# uC_Essentials.net
KiCad netlist of a schematic drawn in Altium Designer
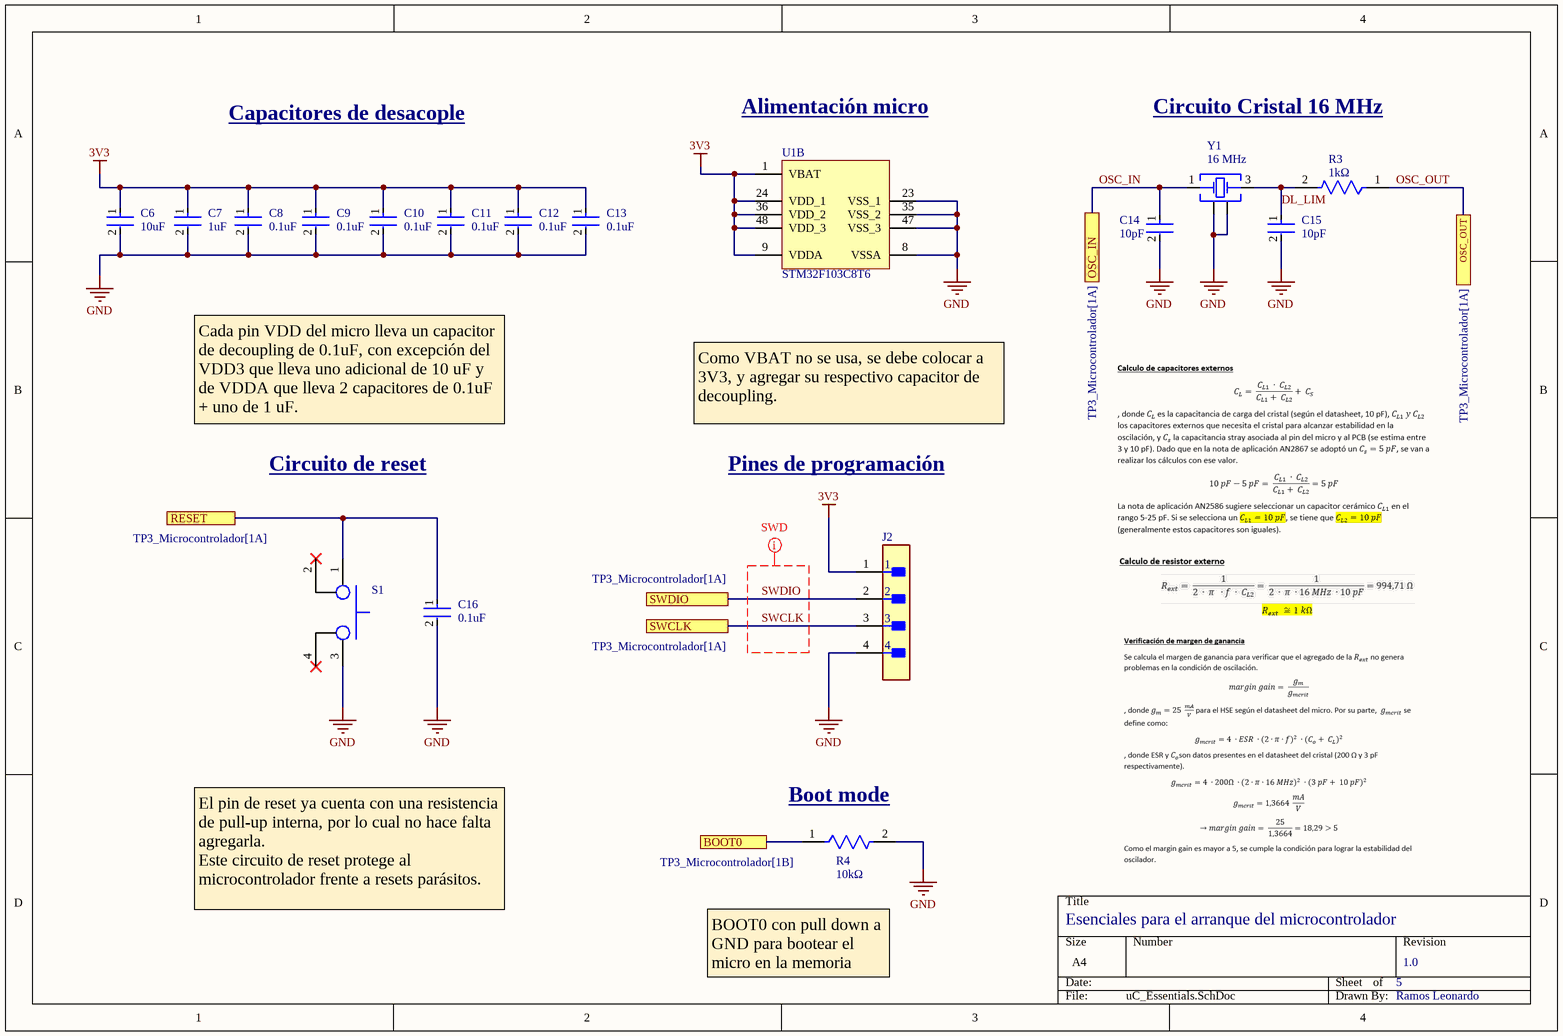
[diagram p0: uC_Essentials.SchDoc]

(export (version "E")
  (design (tool "Eeschema 10.0.6"))
  (components
    (comp (ref "C6")
      (value "10uF")
      (footprint "FP-CC0805-0_85-MFG")
      (description "CAP CER 4.7UF 25V X7R 0805")
      (fields (field (name "MANUFACTURER PART NUMBER") "CC0805KRX7R8BB104") (field (name "TOLERANCE") "0.1"))
      (libsource (lib "Altium Content Vault") (part "11868f565c42a9108669ba33697ecf6"))
    )
    (comp (ref "C7")
      (value "1uF")
      (footprint "FP-CC0805-0_85-MFG")
      (description "CAP CER 1UF 25V X7R 0805")
      (fields (field (name "MANUFACTURER PART NUMBER") "CC0805KRX7R8BB104") (field (name "TOLERANCE") "0.1"))
      (libsource (lib "Altium Content Vault") (part "11868f565c42a9108669ba33697ecf6"))
    )
    (comp (ref "C8")
      (value "0.1uF")
      (footprint "FP-CC0805-0_85-MFG")
      (description "CAP CER 0.1UF 25V X7R 0805")
      (fields (field (name "MANUFACTURER PART NUMBER") "CC0805KRX7R8BB104") (field (name "TOLERANCE") "0.1"))
      (libsource (lib "Altium Content Vault") (part "11868f565c42a9108669ba33697ecf6"))
    )
    (comp (ref "C9")
      (value "0.1uF")
      (footprint "FP-CC0805-0_85-MFG")
      (description "CAP CER 0.1UF 25V X7R 0805")
      (fields (field (name "MANUFACTURER PART NUMBER") "CC0805KRX7R8BB104") (field (name "TOLERANCE") "0.1"))
      (libsource (lib "Altium Content Vault") (part "11868f565c42a9108669ba33697ecf6"))
    )
    (comp (ref "C10")
      (value "0.1uF")
      (footprint "FP-CC0805-0_85-MFG")
      (description "CAP CER 0.1UF 25V X7R 0805")
      (fields (field (name "MANUFACTURER PART NUMBER") "CC0805KRX7R8BB104") (field (name "TOLERANCE") "0.1"))
      (libsource (lib "Altium Content Vault") (part "11868f565c42a9108669ba33697ecf6"))
    )
    (comp (ref "C11")
      (value "0.1uF")
      (footprint "FP-CC0805-0_85-MFG")
      (description "CAP CER 0.1UF 25V X7R 0805")
      (fields (field (name "MANUFACTURER PART NUMBER") "CC0805KRX7R8BB104") (field (name "TOLERANCE") "0.1"))
      (libsource (lib "Altium Content Vault") (part "11868f565c42a9108669ba33697ecf6"))
    )
    (comp (ref "C12")
      (value "0.1uF")
      (footprint "FP-CC0805-0_85-MFG")
      (description "CAP CER 0.1UF 25V X7R 0805")
      (fields (field (name "MANUFACTURER PART NUMBER") "CC0805KRX7R8BB104") (field (name "TOLERANCE") "0.1"))
      (libsource (lib "Altium Content Vault") (part "11868f565c42a9108669ba33697ecf6"))
    )
    (comp (ref "C13")
      (value "0.1uF")
      (footprint "FP-CC0805-0_85-MFG")
      (description "CAP CER 0.1UF 25V X7R 0805")
      (fields (field (name "MANUFACTURER PART NUMBER") "CC0805KRX7R8BB104") (field (name "TOLERANCE") "0.1"))
      (libsource (lib "Altium Content Vault") (part "11868f565c42a9108669ba33697ecf6"))
    )
    (comp (ref "C14")
      (value "10pF")
      (footprint "FP-CC0805-0_85-MFG")
      (description "CAP CER 10pF 25V X7R 0805")
      (fields (field (name "MANUFACTURER PART NUMBER") "CC0805KRX7R8BB104") (field (name "TOLERANCE") "0.1"))
      (libsource (lib "Altium Content Vault") (part "11868f565c42a9108669ba33697ecf6"))
    )
    (comp (ref "C15")
      (value "10pF")
      (footprint "FP-CC0805-0_85-MFG")
      (description "CAP CER 10pF 25V X7R 0805")
      (fields (field (name "MANUFACTURER PART NUMBER") "CC0805KRX7R8BB104") (field (name "TOLERANCE") "0.1"))
      (libsource (lib "Altium Content Vault") (part "11868f565c42a9108669ba33697ecf6"))
    )
    (comp (ref "C16")
      (value "0.1uF")
      (footprint "FP-CC0805-0_85-MFG")
      (description "CAP CER 0.1UF 25V X7R 0805")
      (fields (field (name "MANUFACTURER PART NUMBER") "CC0805KRX7R8BB104") (field (name "TOLERANCE") "0.1"))
      (libsource (lib "Altium Content Vault") (part "11868f565c42a9108669ba33697ecf6"))
    )
    (comp (ref "J2")
      (value "HTSW-104-07-G-S")
      (footprint "FP-HTSW-104-07-G-S-MFG")
      (description "CONN HEADER VERT 4POS 2.54MM")
      (libsource (lib "Altium Content Vault") (part "299a8cea1bdcbc3624fe62c390fa72c"))
    )
    (comp (ref "R3")
      (value "CRCW08054K70JNEA")
      (footprint "FP-CRCW0805-e3-IPC_B")
      (description "RES Thick Film, 1kΩ, 5%, 0.125W, 200ppm/°C, 0805")
      (fields (field (name "TOLERANCE") "5%") (field (name "RESISTANCE") "1kΩ"))
      (libsource (lib "Altium Content Vault") (part "1029c3af85768c4190bb7ad29bc67b5"))
    )
    (comp (ref "R4")
      (value "CRCW08054K70JNEA")
      (footprint "FP-CRCW0805-e3-IPC_B")
      (description "RES Thick Film, 5%, 0.125W, 200ppm/°C, 0805")
      (fields (field (name "TOLERANCE") "5%") (field (name "RESISTANCE") "10kΩ"))
      (libsource (lib "Altium Content Vault") (part "1029c3af85768c4190bb7ad29bc67b5"))
    )
    (comp (ref "S1")
      (value "Tactile push button")
      (footprint "FP-B3W-1000-MFG")
      (libsource (lib "Componentes_custom") (part "Tactile push button"))
    )
    (comp (ref "U1")
      (value "STM32F103C8T6")
      (footprint "STM-LQFP48_L")
      (libsource (lib "Componentes_custom") (part "CMP-0237-00215-3"))
    )
    (comp (ref "Y1")
      (value "16 MHz")
      (footprint "WE-XTAL_IQXC-42")
      (description "830108288709 WE-XTAL Quartz Crystal")
      (libsource (lib "Altium Content Vault") (part "WE-XTAL_IQXC-42"))
    )
  )
  (nets
    (net (code "1") (name "/BOOT0") (class "Default")
      (node (ref "R4") (pin "1") (pinfunction "1_1") (pintype "passive"))
    )
    (net (code "2") (name "/DL_LIM") (class "Default")
      (node (ref "C15") (pin "1") (pinfunction "1_1") (pintype "passive"))
      (node (ref "R3") (pin "2") (pinfunction "2_2") (pintype "passive"))
      (node (ref "Y1") (pin "3") (pinfunction "Crystal_3") (pintype "passive"))
    )
    (net (code "3") (name "/OSC_IN") (class "Default")
      (node (ref "C14") (pin "1") (pinfunction "1_1") (pintype "passive"))
      (node (ref "Y1") (pin "1") (pinfunction "Crystal_1") (pintype "passive"))
    )
    (net (code "4") (name "/OSC_OUT") (class "Default")
      (node (ref "R3") (pin "1") (pinfunction "1_1") (pintype "passive"))
    )
    (net (code "5") (name "/RESET") (class "Default")
      (node (ref "C16") (pin "1") (pinfunction "1_1") (pintype "passive"))
      (node (ref "S1") (pin "1") (pinfunction "1_1") (pintype "passive"))
    )
    (net (code "6") (name "/SWCLK") (class "Default")
      (node (ref "J2") (pin "3") (pinfunction "3_3") (pintype "passive"))
    )
    (net (code "7") (name "/SWDIO") (class "Default")
      (node (ref "J2") (pin "2") (pinfunction "2_2") (pintype "passive"))
    )
    (net (code "8") (name "3V3") (class "Default")
      (node (ref "C10") (pin "1") (pinfunction "1_1") (pintype "passive"))
      (node (ref "C11") (pin "1") (pinfunction "1_1") (pintype "passive"))
      (node (ref "C12") (pin "1") (pinfunction "1_1") (pintype "passive"))
      (node (ref "C13") (pin "1") (pinfunction "1_1") (pintype "passive"))
      (node (ref "C6") (pin "1") (pinfunction "1_1") (pintype "passive"))
      (node (ref "C7") (pin "1") (pinfunction "1_1") (pintype "passive"))
      (node (ref "C8") (pin "1") (pinfunction "1_1") (pintype "passive"))
      (node (ref "C9") (pin "1") (pinfunction "1_1") (pintype "passive"))
      (node (ref "J2") (pin "1") (pinfunction "1_1") (pintype "passive"))
      (node (ref "U1") (pin "1") (pinfunction "VBAT_1") (pintype "power_in"))
      (node (ref "U1") (pin "24") (pinfunction "VDD_1_24") (pintype "power_in"))
      (node (ref "U1") (pin "36") (pinfunction "VDD_2_36") (pintype "power_in"))
      (node (ref "U1") (pin "48") (pinfunction "VDD_3_48") (pintype "power_in"))
      (node (ref "U1") (pin "9") (pinfunction "VDDA_9") (pintype "power_in"))
    )
    (net (code "9") (name "GND") (class "Default")
      (node (ref "C10") (pin "2") (pinfunction "2_2") (pintype "passive"))
      (node (ref "C11") (pin "2") (pinfunction "2_2") (pintype "passive"))
      (node (ref "C12") (pin "2") (pinfunction "2_2") (pintype "passive"))
      (node (ref "C13") (pin "2") (pinfunction "2_2") (pintype "passive"))
      (node (ref "C14") (pin "2") (pinfunction "2_2") (pintype "passive"))
      (node (ref "C15") (pin "2") (pinfunction "2_2") (pintype "passive"))
      (node (ref "C16") (pin "2") (pinfunction "2_2") (pintype "passive"))
      (node (ref "C6") (pin "2") (pinfunction "2_2") (pintype "passive"))
      (node (ref "C7") (pin "2") (pinfunction "2_2") (pintype "passive"))
      (node (ref "C8") (pin "2") (pinfunction "2_2") (pintype "passive"))
      (node (ref "C9") (pin "2") (pinfunction "2_2") (pintype "passive"))
      (node (ref "J2") (pin "4") (pinfunction "4_4") (pintype "passive"))
      (node (ref "R4") (pin "2") (pinfunction "2_2") (pintype "passive"))
      (node (ref "S1") (pin "3") (pinfunction "3_3") (pintype "passive"))
      (node (ref "U1") (pin "23") (pinfunction "VSS_1_23") (pintype "power_in"))
      (node (ref "U1") (pin "35") (pinfunction "VSS_2_35") (pintype "power_in"))
      (node (ref "U1") (pin "47") (pinfunction "VSS_3_47") (pintype "power_in"))
      (node (ref "U1") (pin "8") (pinfunction "VSSA_8") (pintype "power_in"))
      (node (ref "Y1") (pin "2") (pinfunction "GND_2") (pintype "passive"))
      (node (ref "Y1") (pin "4") (pinfunction "GND_4") (pintype "passive"))
    )
    (net (code "10") (name "unconnected-(S1-Pad2)") (class "Default")
      (node (ref "S1") (pin "2") (pinfunction "2_2") (pintype "passive+no_connect"))
    )
    (net (code "11") (name "unconnected-(S1-Pad4)") (class "Default")
      (node (ref "S1") (pin "4") (pinfunction "4_4") (pintype "passive+no_connect"))
    )
  )
)
